# schematic.net
KiCad netlist of a schematic drawn in Altium Designer
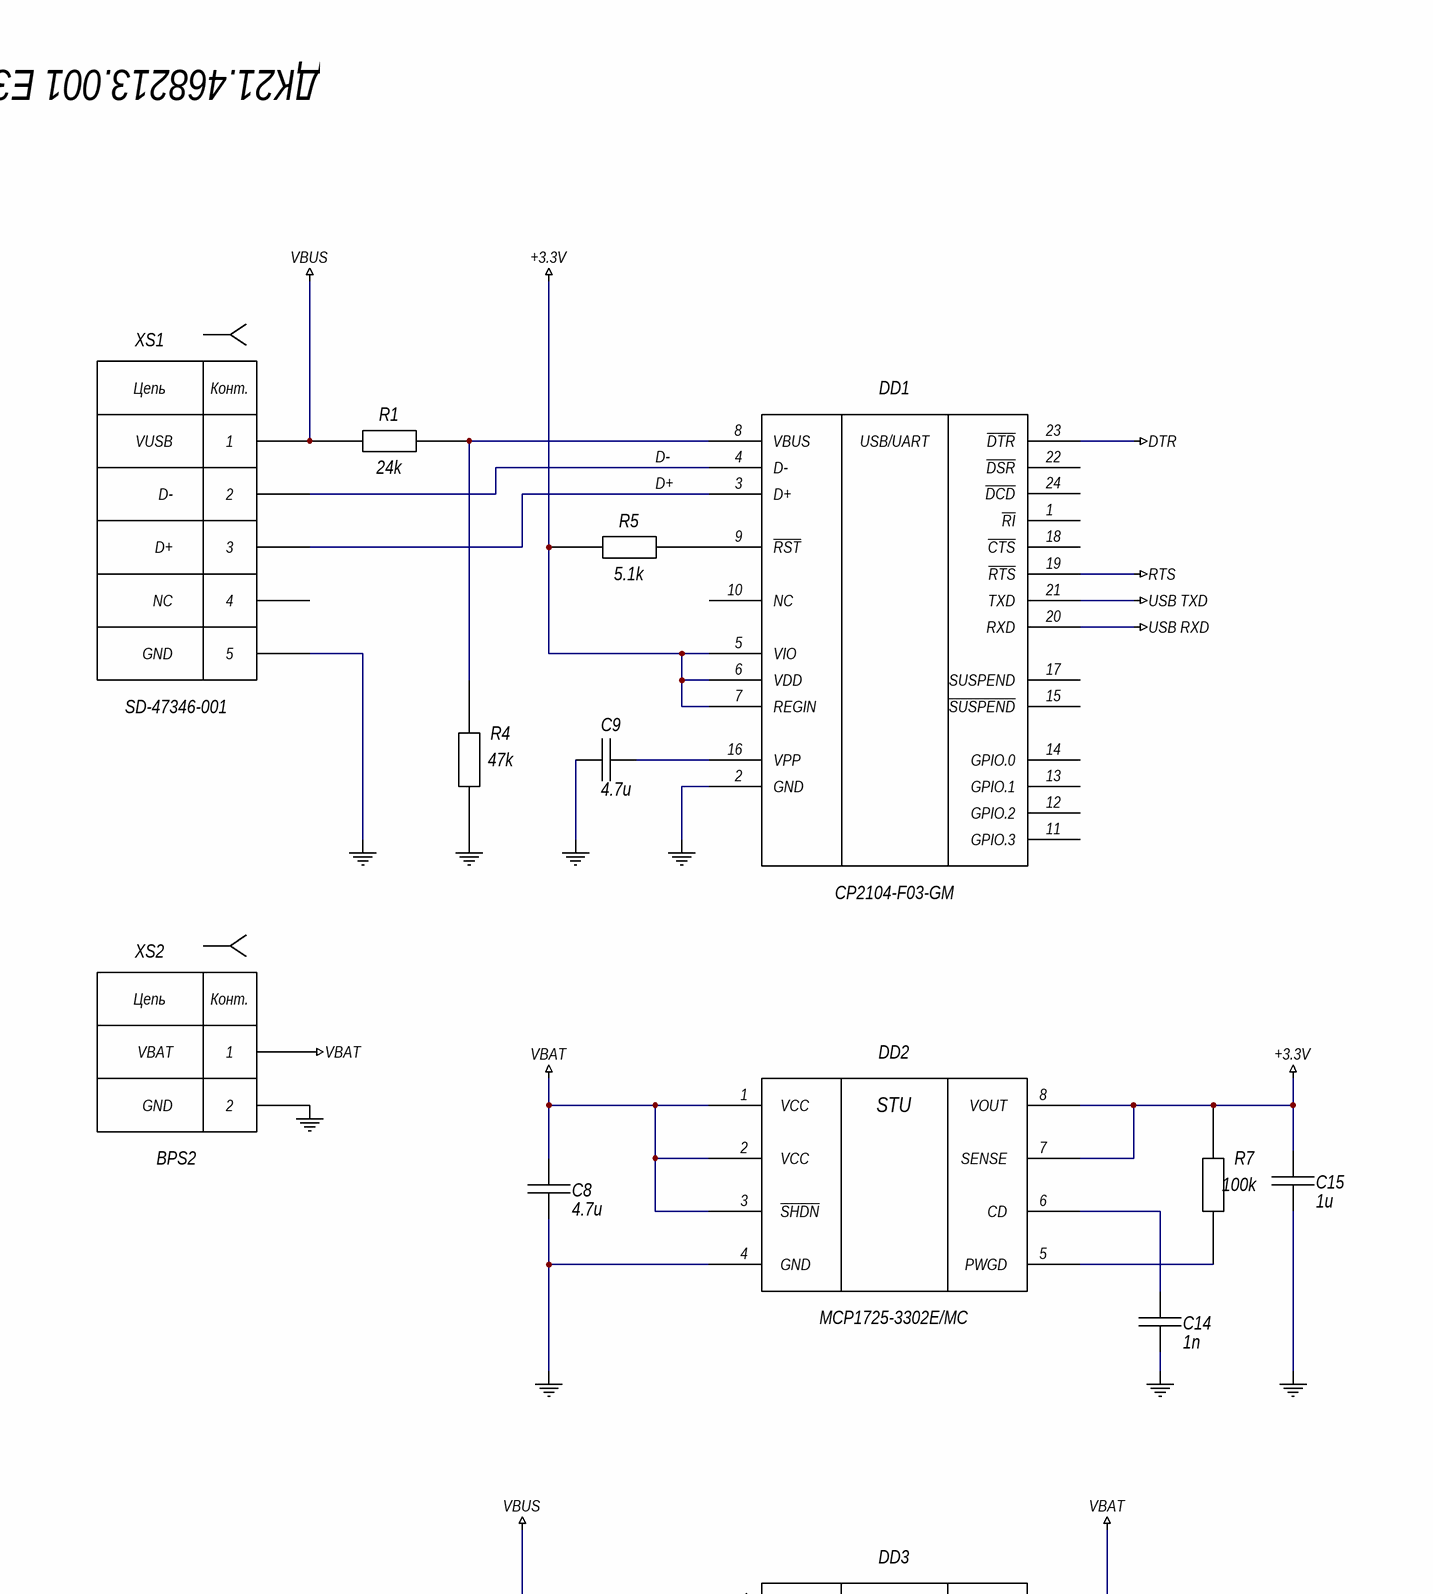
[diagram p0: schematic.SchDoc, top left]
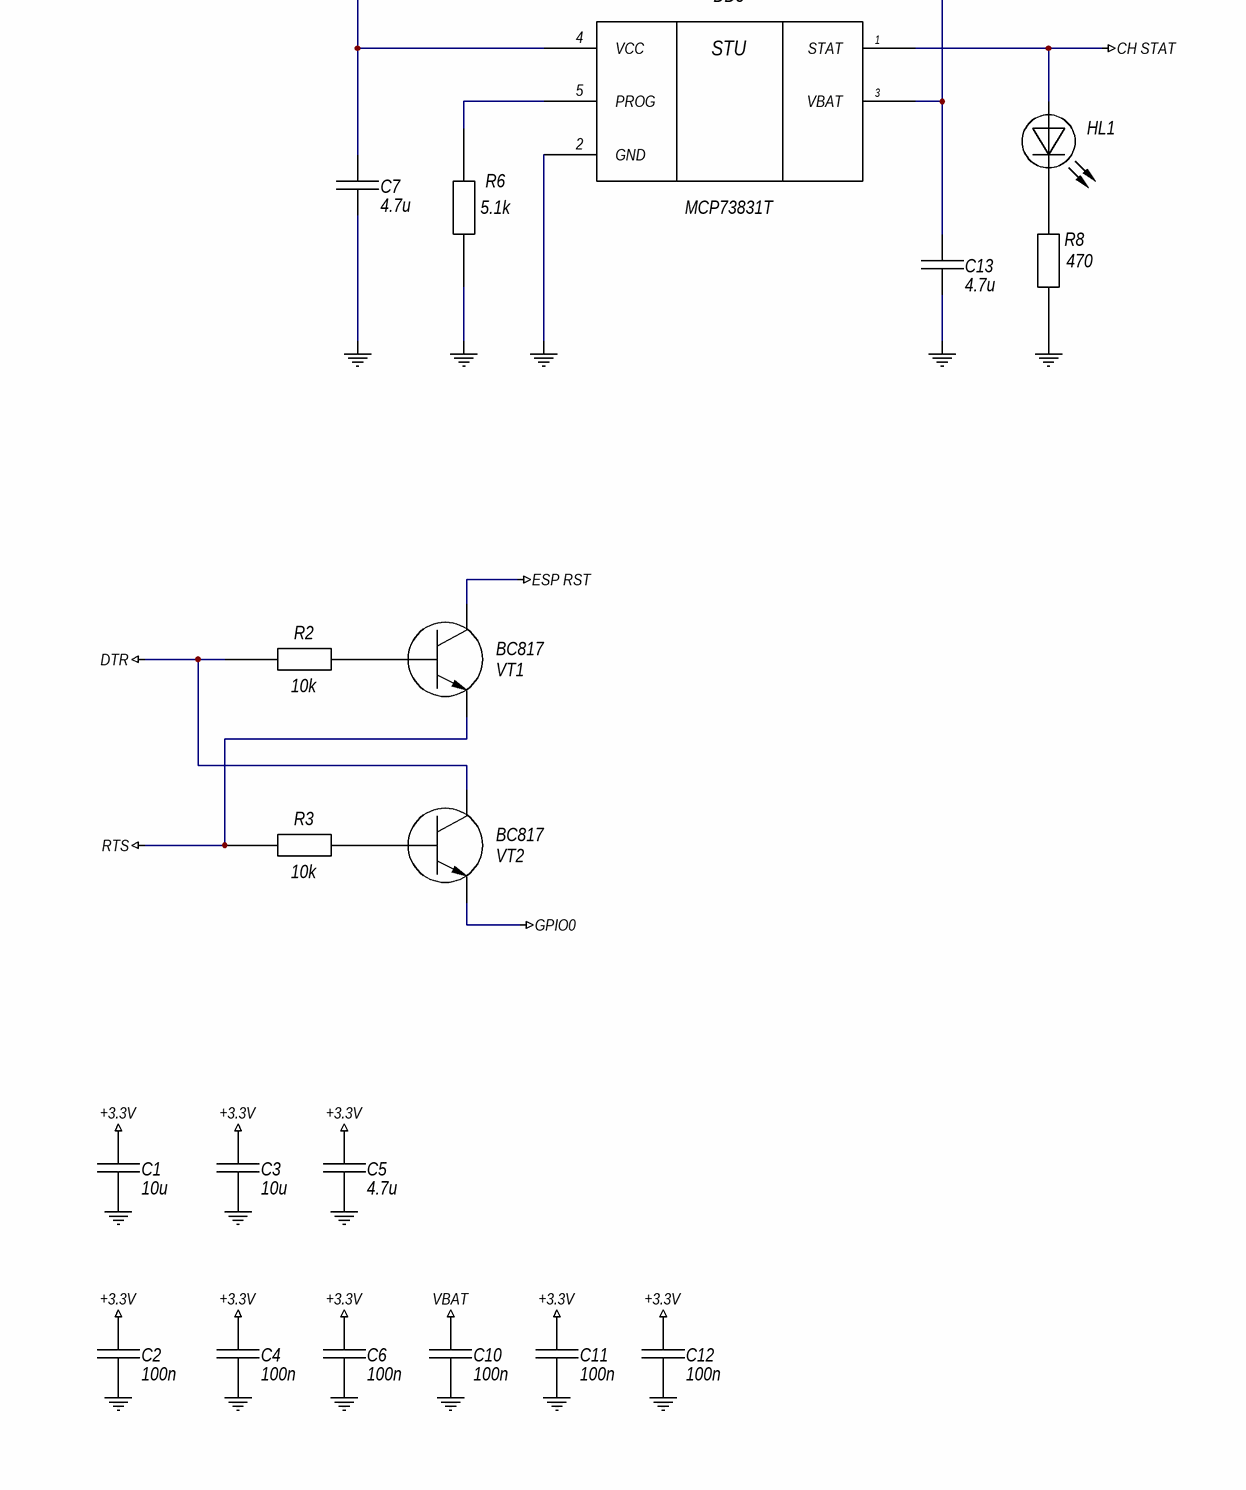
[diagram p1: schematic.SchDoc, bottom left]
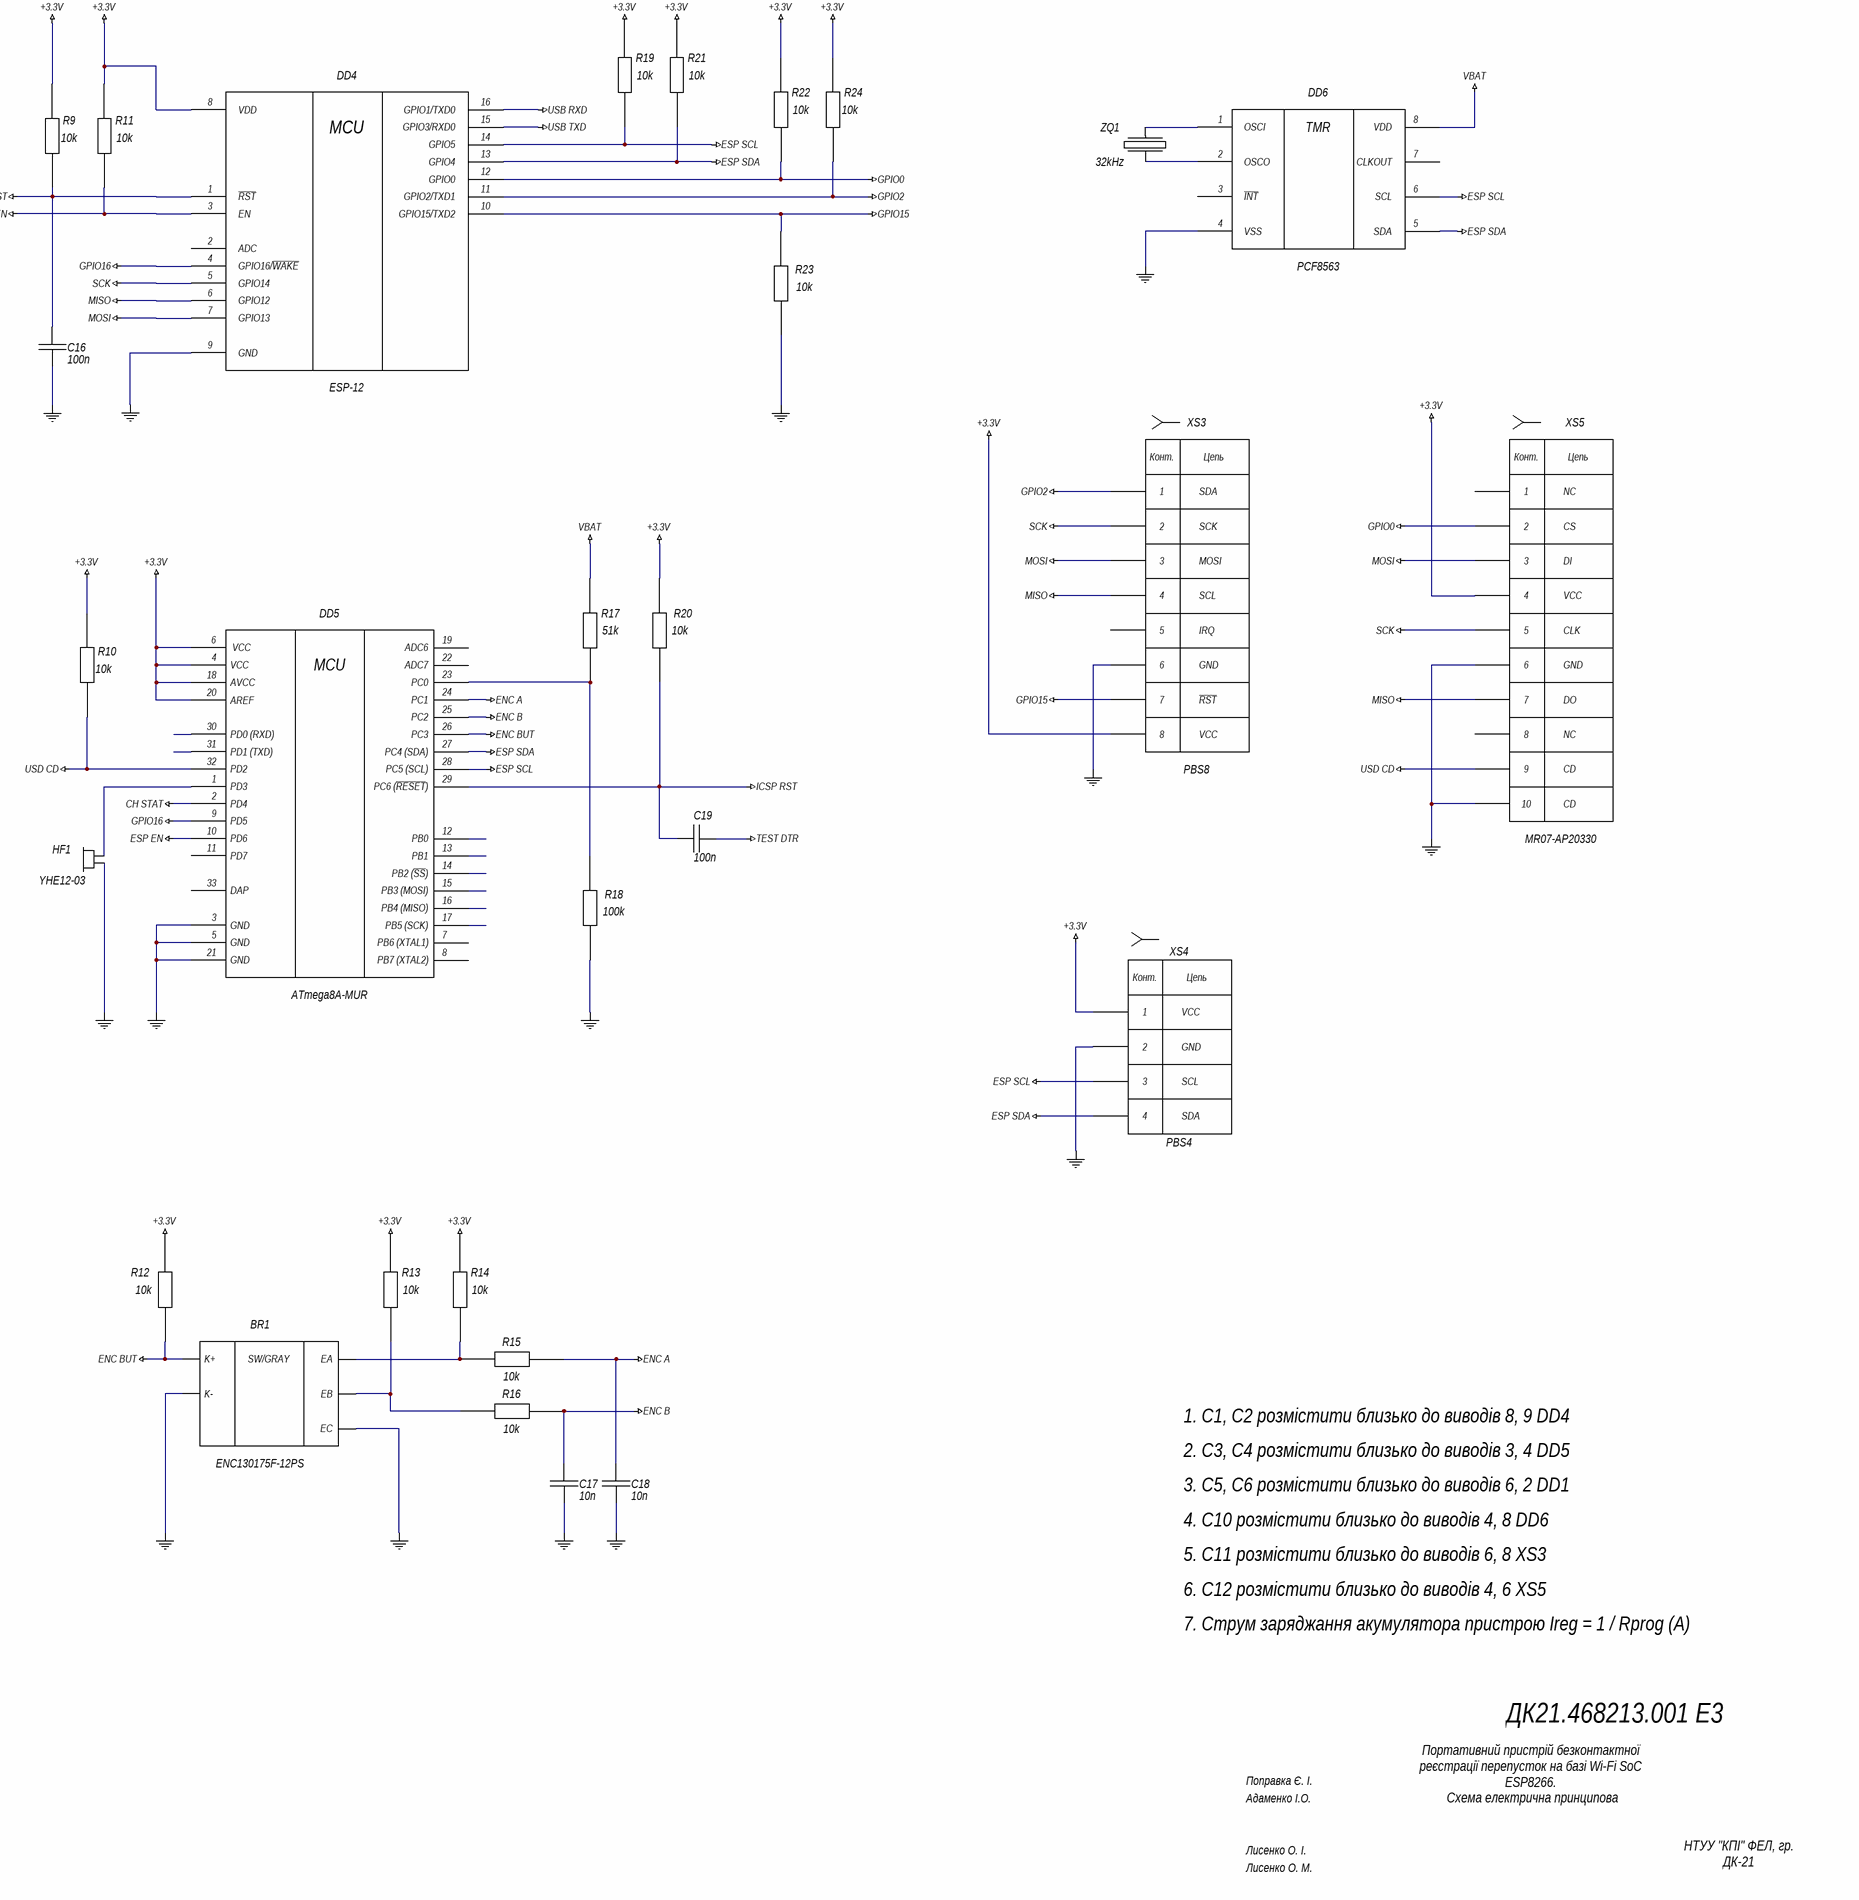
[diagram p2: schematic.SchDoc, bottom right]

(export (version "E")
  (design (tool "Eeschema 10.0.6"))
  (components
    (comp (ref "BR1")
      (value "ENC130175F-12PS")
      (footprint "ENCODER_LED_2")
      (libsource (lib "Symbols GOST") (part "ENC130175F-12PS"))
    )
    (comp (ref "C1")
      (value "10u")
      (footprint "RES0603")
      (description "Chip capasitor")
      (fields (field (name "PART NUMBER") "GRJ32ER71H475KE11") (field (name "VOLTAGE") "50V"))
      (libsource (lib "Symbols GOST") (part "C0805"))
    )
    (comp (ref "C2")
      (value "100n")
      (footprint "RES0603")
      (description "Chip capasitor")
      (fields (field (name "PART NUMBER") "GRJ32ER71H475KE11") (field (name "VOLTAGE") "50V"))
      (libsource (lib "Symbols GOST") (part "C0805"))
    )
    (comp (ref "C3")
      (value "10u")
      (footprint "RES0603")
      (description "Chip capasitor")
      (fields (field (name "PART NUMBER") "GRJ32ER71H475KE11") (field (name "VOLTAGE") "50V"))
      (libsource (lib "Symbols GOST") (part "C0805"))
    )
    (comp (ref "C4")
      (value "100n")
      (footprint "RES0603")
      (description "Chip capasitor")
      (fields (field (name "PART NUMBER") "GRJ32ER71H475KE11") (field (name "VOLTAGE") "50V"))
      (libsource (lib "Symbols GOST") (part "C0805"))
    )
    (comp (ref "C5")
      (value "4.7u")
      (footprint "RES0603")
      (description "Chip capasitor")
      (fields (field (name "PART NUMBER") "GRJ32ER71H475KE11") (field (name "VOLTAGE") "50V"))
      (libsource (lib "Symbols GOST") (part "C0805"))
    )
    (comp (ref "C6")
      (value "100n")
      (footprint "RES0603")
      (description "Chip capasitor")
      (fields (field (name "PART NUMBER") "GRJ32ER71H475KE11") (field (name "VOLTAGE") "50V"))
      (libsource (lib "Symbols GOST") (part "C0805"))
    )
    (comp (ref "C7")
      (value "4.7u")
      (footprint "RES0603")
      (description "Chip capasitor")
      (fields (field (name "PART NUMBER") "GRJ32ER71H475KE11") (field (name "VOLTAGE") "50V"))
      (libsource (lib "Symbols GOST") (part "C0805"))
    )
    (comp (ref "C8")
      (value "4.7u")
      (footprint "RES0603")
      (description "Chip capasitor")
      (fields (field (name "PART NUMBER") "GRJ32ER71H475KE11") (field (name "VOLTAGE") "50V"))
      (libsource (lib "Symbols GOST") (part "C0805"))
    )
    (comp (ref "C9")
      (value "4.7u")
      (footprint "RES0603")
      (description "Chip capasitor")
      (fields (field (name "PART NUMBER") "GRJ32ER71H475KE11") (field (name "VOLTAGE") "50V"))
      (libsource (lib "Symbols GOST") (part "C0805"))
    )
    (comp (ref "C10")
      (value "100n")
      (footprint "RES0603")
      (description "Chip capasitor")
      (fields (field (name "PART NUMBER") "GRJ32ER71H475KE11") (field (name "VOLTAGE") "50V"))
      (libsource (lib "Symbols GOST") (part "C0805"))
    )
    (comp (ref "C11")
      (value "100n")
      (footprint "RES0603")
      (description "Chip capasitor")
      (fields (field (name "PART NUMBER") "GRJ32ER71H475KE11") (field (name "VOLTAGE") "50V"))
      (libsource (lib "Symbols GOST") (part "C0805"))
    )
    (comp (ref "C12")
      (value "100n")
      (footprint "RES0603")
      (description "Chip capasitor")
      (fields (field (name "PART NUMBER") "GRJ32ER71H475KE11") (field (name "VOLTAGE") "50V"))
      (libsource (lib "Symbols GOST") (part "C0805"))
    )
    (comp (ref "C13")
      (value "4.7u")
      (footprint "RES0603")
      (description "Chip capasitor")
      (fields (field (name "PART NUMBER") "GRJ32ER71H475KE11") (field (name "VOLTAGE") "50V"))
      (libsource (lib "Symbols GOST") (part "C0805"))
    )
    (comp (ref "C14")
      (value "1n")
      (footprint "RES0603")
      (description "Chip capasitor")
      (fields (field (name "PART NUMBER") "GRJ32ER71H475KE11") (field (name "VOLTAGE") "50V"))
      (libsource (lib "Symbols GOST") (part "C0805"))
    )
    (comp (ref "C15")
      (value "1u")
      (footprint "RES0603")
      (description "Chip capasitor")
      (fields (field (name "PART NUMBER") "GRJ32ER71H475KE11") (field (name "VOLTAGE") "50V"))
      (libsource (lib "Symbols GOST") (part "C0805"))
    )
    (comp (ref "C16")
      (value "100n")
      (footprint "RES0603")
      (description "Chip capasitor")
      (fields (field (name "PART NUMBER") "GRJ32ER71H475KE11") (field (name "VOLTAGE") "50V"))
      (libsource (lib "Symbols GOST") (part "C0805"))
    )
    (comp (ref "C17")
      (value "10n")
      (footprint "RES0603")
      (description "Chip capasitor")
      (fields (field (name "PART NUMBER") "GRJ32ER71H475KE11") (field (name "VOLTAGE") "50V"))
      (libsource (lib "Symbols GOST") (part "C0805"))
    )
    (comp (ref "C18")
      (value "10n")
      (footprint "RES0603")
      (description "Chip capasitor")
      (fields (field (name "PART NUMBER") "GRJ32ER71H475KE11") (field (name "VOLTAGE") "50V"))
      (libsource (lib "Symbols GOST") (part "C0805"))
    )
    (comp (ref "C19")
      (value "100n")
      (footprint "RES0603")
      (description "Chip capasitor")
      (fields (field (name "PART NUMBER") "GRJ32ER71H475KE11") (field (name "VOLTAGE") "50V"))
      (libsource (lib "Symbols GOST") (part "C0805"))
    )
    (comp (ref "DD1")
      (value "CP2104-F03-GM")
      (footprint "SLAB-QFN-24-2675x2675TP_M")
      (fields (field (name "MANUFACTURER") "Silicon Labs"))
      (libsource (lib "Symbols GOST") (part "CP2104-F03-GM"))
    )
    (comp (ref "DD2")
      (value "MCP1725-3302E/MC")
      (footprint "SOIC127P600X175-8N")
      (description "MCP1725-3302E/MC ULDO")
      (libsource (lib "Symbols GOST") (part "MCP1725-3302E/MC"))
    )
    (comp (ref "DD3")
      (value "MCP73831T")
      (footprint "SOT95P270X145-5N")
      (description "MCP73831T Li-ion/Li-po charger")
      (fields (field (name "PART NUMBER") "MCP73831/2  SOT-23-5"))
      (libsource (lib "Symbols GOST") (part "MCP73831T"))
    )
    (comp (ref "DD4")
      (value "ESP-12")
      (footprint "ESP_12_E")
      (description "ESP-12 Wi-Fi Module")
      (libsource (lib "Symbols GOST") (part "ESP-12E"))
    )
    (comp (ref "DD5")
      (value "ATmega8A-MUR")
      (footprint "QFN127P600-8N")
      (libsource (lib "Symbols GOST") (part "ATmega8A-MUR"))
    )
    (comp (ref "DD6")
      (value "PCF8563")
      (footprint "SOIC8")
      (fields (field (name "PART NUMBER") "MCP1725-3302E/MC"))
      (libsource (lib "Symbols GOST") (part "PCF8563"))
    )
    (comp (ref "HF1")
      (value "YHE12-03")
      (footprint "PCBComponent_1")
      (description "Пьезоизлучатель")
      (libsource (lib "Symbols GOST") (part "HF"))
    )
    (comp (ref "HL1")
      (value "~")
      (footprint "RES0603")
      (description "Светодиод")
      (fields (field (name "PART NUMBER") "KP-2012VGC-A"))
      (libsource (lib "Symbols GOST") (part "HL_02"))
    )
    (comp (ref "R1")
      (value "24k")
      (footprint "RES0603")
      (description "Резистор")
      (fields (field (name "PART NUMBER") "RC0805JR-070RL") (field (name "VOLTAGE") "150V"))
      (libsource (lib "") (part "R0805_3"))
    )
    (comp (ref "R2")
      (value "10k")
      (footprint "RES0603")
      (description "Резистор")
      (fields (field (name "PART NUMBER") "RC0805JR-070RL") (field (name "VOLTAGE") "150V"))
      (libsource (lib "") (part "R0805_2"))
    )
    (comp (ref "R3")
      (value "10k")
      (footprint "RES0603")
      (description "Резистор")
      (fields (field (name "PART NUMBER") "RC0805JR-070RL") (field (name "VOLTAGE") "150V"))
      (libsource (lib "") (part "R0805_2"))
    )
    (comp (ref "R4")
      (value "47k")
      (footprint "RES0603")
      (description "Резистор")
      (fields (field (name "PART NUMBER") "RC0805JR-070RL") (field (name "VOLTAGE") "150V"))
      (libsource (lib "Symbols GOST") (part "R0805"))
    )
    (comp (ref "R5")
      (value "5.1k")
      (footprint "RES0603")
      (description "Резистор")
      (fields (field (name "PART NUMBER") "RC0805JR-070RL") (field (name "VOLTAGE") "150V"))
      (libsource (lib "") (part "R0805_1"))
    )
    (comp (ref "R6")
      (value "5.1k")
      (footprint "RES0603")
      (description "Резистор")
      (fields (field (name "PART NUMBER") "RC0805JR-070RL") (field (name "VOLTAGE") "150V"))
      (libsource (lib "Symbols GOST") (part "R0805"))
    )
    (comp (ref "R7")
      (value "100k")
      (footprint "RES0603")
      (description "Резистор")
      (fields (field (name "PART NUMBER") "RC0805JR-070RL") (field (name "VOLTAGE") "150V"))
      (libsource (lib "Symbols GOST") (part "R0805"))
    )
    (comp (ref "R8")
      (value "470")
      (footprint "RES0603")
      (description "Резистор")
      (fields (field (name "PART NUMBER") "RC0805JR-070RL") (field (name "VOLTAGE") "150V"))
      (libsource (lib "Symbols GOST") (part "R0805"))
    )
    (comp (ref "R9")
      (value "10k")
      (footprint "RES0603")
      (description "Резистор")
      (fields (field (name "PART NUMBER") "RC0805JR-070RL") (field (name "VOLTAGE") "150V"))
      (libsource (lib "Symbols GOST") (part "R0805"))
    )
    (comp (ref "R10")
      (value "10k")
      (footprint "RES0603")
      (description "Резистор")
      (fields (field (name "PART NUMBER") "RC0805JR-070RL") (field (name "VOLTAGE") "150V"))
      (libsource (lib "Symbols GOST") (part "R0805"))
    )
    (comp (ref "R11")
      (value "10k")
      (footprint "RES0603")
      (description "Резистор")
      (fields (field (name "PART NUMBER") "RC0805JR-070RL") (field (name "VOLTAGE") "150V"))
      (libsource (lib "Symbols GOST") (part "R0805"))
    )
    (comp (ref "R12")
      (value "10k")
      (footprint "RES0603")
      (description "Резистор")
      (fields (field (name "PART NUMBER") "RC0805JR-070RL") (field (name "VOLTAGE") "150V"))
      (libsource (lib "") (part "R0805_1"))
    )
    (comp (ref "R13")
      (value "10k")
      (footprint "RES0603")
      (description "Резистор")
      (fields (field (name "PART NUMBER") "RC0805JR-070RL") (field (name "VOLTAGE") "150V"))
      (libsource (lib "Symbols GOST") (part "R0805"))
    )
    (comp (ref "R14")
      (value "10k")
      (footprint "RES0603")
      (description "Резистор")
      (fields (field (name "PART NUMBER") "RC0805JR-070RL") (field (name "VOLTAGE") "150V"))
      (libsource (lib "Symbols GOST") (part "R0805"))
    )
    (comp (ref "R15")
      (value "10k")
      (footprint "RES0603")
      (description "Резистор")
      (fields (field (name "PART NUMBER") "RC0805JR-070RL") (field (name "VOLTAGE") "150V"))
      (libsource (lib "") (part "R0805_1"))
    )
    (comp (ref "R16")
      (value "10k")
      (footprint "RES0603")
      (description "Резистор")
      (fields (field (name "PART NUMBER") "RC0805JR-070RL") (field (name "VOLTAGE") "150V"))
      (libsource (lib "") (part "R0805_1"))
    )
    (comp (ref "R17")
      (value "51k")
      (footprint "RES0603")
      (description "Резистор")
      (fields (field (name "PART NUMBER") "RC0805JR-070RL") (field (name "VOLTAGE") "150V"))
      (libsource (lib "Symbols GOST") (part "R0805"))
    )
    (comp (ref "R18")
      (value "100k")
      (footprint "RES0603")
      (description "Резистор")
      (fields (field (name "PART NUMBER") "RC0805JR-070RL") (field (name "VOLTAGE") "150V"))
      (libsource (lib "Symbols GOST") (part "R0805"))
    )
    (comp (ref "R19")
      (value "10k")
      (footprint "RES0603")
      (description "Резистор")
      (fields (field (name "PART NUMBER") "RC0805JR-070RL") (field (name "VOLTAGE") "150V"))
      (libsource (lib "Symbols GOST") (part "R0805"))
    )
    (comp (ref "R20")
      (value "10k")
      (footprint "RES0603")
      (description "Резистор")
      (fields (field (name "PART NUMBER") "RC0805JR-070RL") (field (name "VOLTAGE") "150V"))
      (libsource (lib "Symbols GOST") (part "R0805"))
    )
    (comp (ref "R21")
      (value "10k")
      (footprint "RES0603")
      (description "Резистор")
      (fields (field (name "PART NUMBER") "RC0805JR-070RL") (field (name "VOLTAGE") "150V"))
      (libsource (lib "Symbols GOST") (part "R0805"))
    )
    (comp (ref "R22")
      (value "10k")
      (footprint "RES0603")
      (description "Резистор")
      (fields (field (name "PART NUMBER") "RC0805JR-070RL") (field (name "VOLTAGE") "150V"))
      (libsource (lib "Symbols GOST") (part "R0805"))
    )
    (comp (ref "R23")
      (value "10k")
      (footprint "RES0603")
      (description "Резистор")
      (fields (field (name "PART NUMBER") "RC0805JR-070RL") (field (name "VOLTAGE") "150V"))
      (libsource (lib "Symbols GOST") (part "R0805"))
    )
    (comp (ref "R24")
      (value "10k")
      (footprint "RES0603")
      (description "Резистор")
      (fields (field (name "PART NUMBER") "RC0805JR-070RL") (field (name "VOLTAGE") "150V"))
      (libsource (lib "Symbols GOST") (part "R0805"))
    )
    (comp (ref "VT1")
      (value "BC817")
      (footprint "SOT95P245X110-3N")
      (description "Транзистор биполярный, NPN")
      (libsource (lib "Symbols GOST") (part "VT_01"))
    )
    (comp (ref "VT2")
      (value "BC817")
      (footprint "SOT95P245X110-3N")
      (description "Транзистор биполярный, NPN")
      (libsource (lib "Symbols GOST") (part "VT_01"))
    )
    (comp (ref "XS1")
      (value "SD-47346-001")
      (footprint "USB-MICROB")
      (description "micro USB")
      (fields (field (name "PART NUMBER") "RFID-RC522 MFRC522 модуль"))
      (libsource (lib "Symbols GOST") (part "usb"))
    )
    (comp (ref "XS2")
      (value "BPS2")
      (footprint "PCBComponent_1 - duplicate")
      (description "battery")
      (fields (field (name "PART NUMBER") "RFID-RC522 MFRC522 модуль"))
      (libsource (lib "Symbols GOST") (part "lipo"))
    )
    (comp (ref "XS3")
      (value "PBS8")
      (footprint "RFID-RC522")
      (description "RC522 RFID module")
      (fields (field (name "PART NUMBER") "RFID-RC522 MFRC522 модуль"))
      (libsource (lib "Symbols GOST") (part "RC522"))
    )
    (comp (ref "XS4")
      (value "PBS4")
      (footprint "SSD")
      (description "SSD1306 OLED Screen Module")
      (fields (field (name "PART NUMBER") "RFID-RC522 MFRC522 модуль"))
      (libsource (lib "Symbols GOST") (part "SSD1306"))
    )
    (comp (ref "XS5")
      (value "MR07-AP20330")
      (footprint "MICROSD Slot")
      (description "RC522 RFID module")
      (fields (field (name "PART NUMBER") "RFID-RC522 MFRC522 модуль"))
      (libsource (lib "Symbols GOST") (part "uSD"))
    )
    (comp (ref "ZQ1")
      (value "32kHz")
      (footprint "PCBComponent_1 - duplicate1")
      (description "Элемент пьезоэлектрический с двумя выводами")
      (fields (field (name "PART NUMBER") "HC49/US 16MHz"))
      (libsource (lib "Symbols GOST") (part "ZQ_01"))
    )
  )
  (nets
    (net (code "1") (name "+3.3V") (class "Default")
      (node (ref "C1") (pin "1") (pinfunction "1_1") (pintype "passive"))
      (node (ref "C11") (pin "1") (pinfunction "1_1") (pintype "passive"))
      (node (ref "C12") (pin "1") (pinfunction "1_1") (pintype "passive"))
      (node (ref "C15") (pin "1") (pinfunction "1_1") (pintype "passive"))
      (node (ref "C2") (pin "1") (pinfunction "1_1") (pintype "passive"))
      (node (ref "C3") (pin "1") (pinfunction "1_1") (pintype "passive"))
      (node (ref "C4") (pin "1") (pinfunction "1_1") (pintype "passive"))
      (node (ref "C5") (pin "1") (pinfunction "1_1") (pintype "passive"))
      (node (ref "C6") (pin "1") (pinfunction "1_1") (pintype "passive"))
      (node (ref "DD1") (pin "5") (pinfunction "VIO_5") (pintype "passive"))
      (node (ref "DD1") (pin "6") (pinfunction "VDD_6") (pintype "passive"))
      (node (ref "DD1") (pin "7") (pinfunction "REGIN_7") (pintype "passive"))
      (node (ref "DD2") (pin "7") (pinfunction "SENSE_7") (pintype "passive"))
      (node (ref "DD2") (pin "8") (pinfunction "VOUT_8") (pintype "passive"))
      (node (ref "DD4") (pin "8") (pinfunction "VDD_8") (pintype "passive"))
      (node (ref "DD5") (pin "18") (pinfunction "AVCC_18") (pintype "passive"))
      (node (ref "DD5") (pin "20") (pinfunction "AREF_20") (pintype "passive"))
      (node (ref "DD5") (pin "4") (pinfunction "VCC_4") (pintype "passive"))
      (node (ref "DD5") (pin "6") (pinfunction "VCC_6") (pintype "passive"))
      (node (ref "R10") (pin "2") (pinfunction "Terminal_B_2") (pintype "passive"))
      (node (ref "R11") (pin "2") (pinfunction "Terminal_B_2") (pintype "passive"))
      (node (ref "R12") (pin "2") (pinfunction "Terminal_B_2") (pintype "passive"))
      (node (ref "R13") (pin "2") (pinfunction "Terminal_B_2") (pintype "passive"))
      (node (ref "R14") (pin "2") (pinfunction "Terminal_B_2") (pintype "passive"))
      (node (ref "R19") (pin "2") (pinfunction "Terminal_B_2") (pintype "passive"))
      (node (ref "R20") (pin "2") (pinfunction "Terminal_B_2") (pintype "passive"))
      (node (ref "R21") (pin "2") (pinfunction "Terminal_B_2") (pintype "passive"))
      (node (ref "R22") (pin "2") (pinfunction "Terminal_B_2") (pintype "passive"))
      (node (ref "R24") (pin "2") (pinfunction "Terminal_B_2") (pintype "passive"))
      (node (ref "R5") (pin "1") (pinfunction "Terminal_A_1") (pintype "passive"))
      (node (ref "R7") (pin "2") (pinfunction "Terminal_B_2") (pintype "passive"))
      (node (ref "R9") (pin "2") (pinfunction "Terminal_B_2") (pintype "passive"))
      (node (ref "XS3") (pin "8") (pinfunction "VCC_8") (pintype "passive"))
      (node (ref "XS4") (pin "1") (pinfunction "VCC_1") (pintype "passive"))
      (node (ref "XS5") (pin "4") (pinfunction "VCC_4") (pintype "passive"))
    )
    (net (code "2") (name "/D+") (class "Default")
      (node (ref "DD1") (pin "3") (pinfunction "D+_3") (pintype "passive"))
      (node (ref "XS1") (pin "3") (pinfunction "D+_3") (pintype "passive"))
    )
    (net (code "3") (name "/D-") (class "Default")
      (node (ref "DD1") (pin "4") (pinfunction "D-_4") (pintype "passive"))
      (node (ref "XS1") (pin "2") (pinfunction "D-_2") (pintype "passive"))
    )
    (net (code "4") (name "CH STAT") (class "Default")
      (node (ref "DD3") (pin "1") (pinfunction "STAT_1") (pintype "passive"))
      (node (ref "DD5") (pin "2") (pinfunction "PD4_2") (pintype "passive"))
      (node (ref "HL1") (pin "1") (pinfunction "A_1") (pintype "passive"))
    )
    (net (code "5") (name "DTR") (class "Default")
      (node (ref "DD1") (pin "23") (pinfunction "~{DTR}_23") (pintype "passive"))
      (node (ref "R2") (pin "2") (pinfunction "Terminal_B_2") (pintype "passive"))
      (node (ref "VT2") (pin "3") (pinfunction "K_3") (pintype "passive"))
    )
    (net (code "6") (name "ENC A") (class "Default")
      (node (ref "C18") (pin "1") (pinfunction "1_1") (pintype "passive"))
      (node (ref "DD5") (pin "24") (pinfunction "PC1_24") (pintype "passive"))
      (node (ref "R15") (pin "2") (pinfunction "Terminal_B_2") (pintype "passive"))
    )
    (net (code "7") (name "ENC B") (class "Default")
      (node (ref "C17") (pin "1") (pinfunction "1_1") (pintype "passive"))
      (node (ref "DD5") (pin "25") (pinfunction "PC2_25") (pintype "passive"))
      (node (ref "R16") (pin "2") (pinfunction "Terminal_B_2") (pintype "passive"))
    )
    (net (code "8") (name "ENC BUT") (class "Default")
      (node (ref "BR1") (pin "K+") (pinfunction "K+_K+") (pintype "passive"))
      (node (ref "DD5") (pin "26") (pinfunction "PC3_26") (pintype "passive"))
      (node (ref "R12") (pin "1") (pinfunction "Terminal_A_1") (pintype "passive"))
    )
    (net (code "9") (name "ESP EN") (class "Default")
      (node (ref "DD4") (pin "3") (pinfunction "EN_3") (pintype "passive"))
      (node (ref "DD5") (pin "10") (pinfunction "PD6_10") (pintype "passive"))
      (node (ref "R11") (pin "1") (pinfunction "Terminal_A_1") (pintype "passive"))
    )
    (net (code "10") (name "ESP RST") (class "Default")
      (node (ref "C16") (pin "1") (pinfunction "1_1") (pintype "passive"))
      (node (ref "DD4") (pin "1") (pinfunction "~{RST}_1") (pintype "passive"))
      (node (ref "R9") (pin "1") (pinfunction "Terminal_A_1") (pintype "passive"))
      (node (ref "VT1") (pin "3") (pinfunction "K_3") (pintype "passive"))
    )
    (net (code "11") (name "ESP SCL") (class "Default")
      (node (ref "DD4") (pin "14") (pinfunction "GPIO5_14") (pintype "passive"))
      (node (ref "DD5") (pin "28") (pinfunction "PC5_(SCL)_28") (pintype "passive"))
      (node (ref "DD6") (pin "6") (pinfunction "SCL_6") (pintype "passive"))
      (node (ref "R19") (pin "1") (pinfunction "Terminal_A_1") (pintype "passive"))
      (node (ref "XS4") (pin "3") (pinfunction "SCL_3") (pintype "passive"))
    )
    (net (code "12") (name "ESP SDA") (class "Default")
      (node (ref "DD4") (pin "13") (pinfunction "GPIO4_13") (pintype "passive"))
      (node (ref "DD5") (pin "27") (pinfunction "PC4_(SDA)_27") (pintype "passive"))
      (node (ref "DD6") (pin "5") (pinfunction "SDA_5") (pintype "passive"))
      (node (ref "R21") (pin "1") (pinfunction "Terminal_A_1") (pintype "passive"))
      (node (ref "XS4") (pin "4") (pinfunction "SDA_4") (pintype "passive"))
    )
    (net (code "13") (name "GND") (class "Default")
      (node (ref "BR1") (pin "EC") (pinfunction "EC_EC") (pintype "passive"))
      (node (ref "BR1") (pin "K-") (pinfunction "K-_K-") (pintype "passive"))
      (node (ref "C1") (pin "2") (pinfunction "2_2") (pintype "passive"))
      (node (ref "C10") (pin "2") (pinfunction "2_2") (pintype "passive"))
      (node (ref "C11") (pin "2") (pinfunction "2_2") (pintype "passive"))
      (node (ref "C12") (pin "2") (pinfunction "2_2") (pintype "passive"))
      (node (ref "C13") (pin "2") (pinfunction "2_2") (pintype "passive"))
      (node (ref "C14") (pin "2") (pinfunction "2_2") (pintype "passive"))
      (node (ref "C15") (pin "2") (pinfunction "2_2") (pintype "passive"))
      (node (ref "C16") (pin "2") (pinfunction "2_2") (pintype "passive"))
      (node (ref "C17") (pin "2") (pinfunction "2_2") (pintype "passive"))
      (node (ref "C18") (pin "2") (pinfunction "2_2") (pintype "passive"))
      (node (ref "C2") (pin "2") (pinfunction "2_2") (pintype "passive"))
      (node (ref "C3") (pin "2") (pinfunction "2_2") (pintype "passive"))
      (node (ref "C4") (pin "2") (pinfunction "2_2") (pintype "passive"))
      (node (ref "C5") (pin "2") (pinfunction "2_2") (pintype "passive"))
      (node (ref "C6") (pin "2") (pinfunction "2_2") (pintype "passive"))
      (node (ref "C7") (pin "2") (pinfunction "2_2") (pintype "passive"))
      (node (ref "C8") (pin "2") (pinfunction "2_2") (pintype "passive"))
      (node (ref "C9") (pin "2") (pinfunction "2_2") (pintype "passive"))
      (node (ref "DD1") (pin "2") (pinfunction "GND_2") (pintype "passive"))
      (node (ref "DD2") (pin "4") (pinfunction "GND_4") (pintype "passive"))
      (node (ref "DD3") (pin "2") (pinfunction "GND_2") (pintype "passive"))
      (node (ref "DD4") (pin "9") (pinfunction "GND_9") (pintype "passive"))
      (node (ref "DD5") (pin "21") (pinfunction "GND_21") (pintype "passive"))
      (node (ref "DD5") (pin "3") (pinfunction "GND_3") (pintype "passive"))
      (node (ref "DD5") (pin "5") (pinfunction "GND_5") (pintype "passive"))
      (node (ref "DD6") (pin "4") (pinfunction "VSS_4") (pintype "passive"))
      (node (ref "HF1") (pin "1") (pinfunction "Terminal_A_1") (pintype "passive"))
      (node (ref "R18") (pin "1") (pinfunction "Terminal_A_1") (pintype "passive"))
      (node (ref "R23") (pin "1") (pinfunction "Terminal_A_1") (pintype "passive"))
      (node (ref "R4") (pin "1") (pinfunction "Terminal_A_1") (pintype "passive"))
      (node (ref "R6") (pin "1") (pinfunction "Terminal_A_1") (pintype "passive"))
      (node (ref "R8") (pin "1") (pinfunction "Terminal_A_1") (pintype "passive"))
      (node (ref "XS1") (pin "5") (pinfunction "GND_5") (pintype "passive"))
      (node (ref "XS2") (pin "2") (pinfunction "GND_2") (pintype "passive"))
      (node (ref "XS3") (pin "6") (pinfunction "GND_6") (pintype "passive"))
      (node (ref "XS4") (pin "2") (pinfunction "GND_2") (pintype "passive"))
      (node (ref "XS5") (pin "10") (pinfunction "CD_10") (pintype "passive"))
      (node (ref "XS5") (pin "6") (pinfunction "GND_6") (pintype "passive"))
    )
    (net (code "14") (name "GPIO0") (class "Default")
      (node (ref "DD4") (pin "12") (pinfunction "GPIO0_12") (pintype "passive"))
      (node (ref "R22") (pin "1") (pinfunction "Terminal_A_1") (pintype "passive"))
      (node (ref "VT2") (pin "2") (pinfunction "E_2") (pintype "passive"))
      (node (ref "XS5") (pin "2") (pinfunction "CS_2") (pintype "passive"))
    )
    (net (code "15") (name "GPIO2") (class "Default")
      (node (ref "DD4") (pin "11") (pinfunction "GPIO2/TXD1_11") (pintype "passive"))
      (node (ref "R24") (pin "1") (pinfunction "Terminal_A_1") (pintype "passive"))
      (node (ref "XS3") (pin "1") (pinfunction "SDA_1") (pintype "passive"))
    )
    (net (code "16") (name "GPIO15") (class "Default")
      (node (ref "DD4") (pin "10") (pinfunction "GPIO15/TXD2_10") (pintype "passive"))
      (node (ref "R23") (pin "2") (pinfunction "Terminal_B_2") (pintype "passive"))
      (node (ref "XS3") (pin "7") (pinfunction "~{RST}_7") (pintype "passive"))
    )
    (net (code "17") (name "GPIO16") (class "Default")
      (node (ref "DD4") (pin "4") (pinfunction "GPIO16/~{WAKE}_4") (pintype "passive"))
      (node (ref "DD5") (pin "9") (pinfunction "PD5_9") (pintype "passive"))
    )
    (net (code "18") (name "ICSP RST") (class "Default")
      (node (ref "C19") (pin "1") (pinfunction "1_1") (pintype "passive"))
      (node (ref "DD5") (pin "29") (pinfunction "PC6_(~{RESET})_29") (pintype "passive"))
      (node (ref "R20") (pin "1") (pinfunction "Terminal_A_1") (pintype "passive"))
    )
    (net (code "19") (name "MISO") (class "Default")
      (node (ref "DD4") (pin "6") (pinfunction "GPIO12_6") (pintype "passive"))
      (node (ref "XS3") (pin "4") (pinfunction "SCL_4") (pintype "passive"))
      (node (ref "XS5") (pin "7") (pinfunction "DO_7") (pintype "passive"))
    )
    (net (code "20") (name "MOSI") (class "Default")
      (node (ref "DD4") (pin "7") (pinfunction "GPIO13_7") (pintype "passive"))
      (node (ref "XS3") (pin "3") (pinfunction "MOSI_3") (pintype "passive"))
      (node (ref "XS5") (pin "3") (pinfunction "DI_3") (pintype "passive"))
    )
    (net (code "21") (name "Net-(DD1-VBUS)") (class "Default")
      (node (ref "DD1") (pin "8") (pinfunction "VBUS_8") (pintype "passive"))
      (node (ref "R1") (pin "1") (pinfunction "Terminal_A_1") (pintype "passive"))
      (node (ref "R4") (pin "2") (pinfunction "Terminal_B_2") (pintype "passive"))
    )
    (net (code "22") (name "Net-(DD1-VPP)") (class "Default")
      (node (ref "C9") (pin "1") (pinfunction "1_1") (pintype "passive"))
      (node (ref "DD1") (pin "16") (pinfunction "VPP_16") (pintype "passive"))
    )
    (net (code "23") (name "Net-(DD1-~{RST})") (class "Default")
      (node (ref "DD1") (pin "9") (pinfunction "~{RST}_9") (pintype "passive"))
      (node (ref "R5") (pin "2") (pinfunction "Terminal_B_2") (pintype "passive"))
    )
    (net (code "24") (name "Net-(DD2-CD)") (class "Default")
      (node (ref "C14") (pin "1") (pinfunction "1_1") (pintype "passive"))
      (node (ref "DD2") (pin "6") (pinfunction "CD_6") (pintype "passive"))
    )
    (net (code "25") (name "Net-(DD2-PWGD)") (class "Default")
      (node (ref "DD2") (pin "5") (pinfunction "PWGD_5") (pintype "passive"))
      (node (ref "R7") (pin "1") (pinfunction "Terminal_A_1") (pintype "passive"))
    )
    (net (code "26") (name "Net-(DD3-PROG)") (class "Default")
      (node (ref "DD3") (pin "5") (pinfunction "PROG_5") (pintype "passive"))
      (node (ref "R6") (pin "2") (pinfunction "Terminal_B_2") (pintype "passive"))
    )
    (net (code "27") (name "Net-(DD5-PC0)") (class "Default")
      (node (ref "DD5") (pin "23") (pinfunction "PC0_23") (pintype "passive"))
      (node (ref "R17") (pin "1") (pinfunction "Terminal_A_1") (pintype "passive"))
      (node (ref "R18") (pin "2") (pinfunction "Terminal_B_2") (pintype "passive"))
    )
    (net (code "28") (name "Net-(DD5-PD3)") (class "Default")
      (node (ref "DD5") (pin "1") (pinfunction "PD3_1") (pintype "passive"))
      (node (ref "HF1") (pin "2") (pinfunction "Terminal_B_2") (pintype "passive"))
    )
    (net (code "29") (name "Net-(DD6-OSCI)") (class "Default")
      (node (ref "DD6") (pin "1") (pinfunction "OSCI_1") (pintype "passive"))
      (node (ref "ZQ1") (pin "1") (pintype "passive"))
    )
    (net (code "30") (name "Net-(DD6-OSCO)") (class "Default")
      (node (ref "DD6") (pin "2") (pinfunction "OSCO_2") (pintype "passive"))
      (node (ref "ZQ1") (pin "2") (pintype "passive"))
    )
    (net (code "31") (name "Net-(HL1-K)") (class "Default")
      (node (ref "HL1") (pin "2") (pinfunction "K_2") (pintype "passive"))
      (node (ref "R8") (pin "2") (pinfunction "Terminal_B_2") (pintype "passive"))
    )
    (net (code "32") (name "Net-(R2-Terminal_A)") (class "Default")
      (node (ref "R2") (pin "1") (pinfunction "Terminal_A_1") (pintype "passive"))
      (node (ref "VT1") (pin "1") (pinfunction "B_1") (pintype "passive"))
    )
    (net (code "33") (name "Net-(R3-Terminal_A)") (class "Default")
      (node (ref "R3") (pin "1") (pinfunction "Terminal_A_1") (pintype "passive"))
      (node (ref "VT2") (pin "1") (pinfunction "B_1") (pintype "passive"))
    )
    (net (code "34") (name "Net-(R13-Terminal_A)") (class "Default")
      (node (ref "BR1") (pin "EB") (pinfunction "EB_EB") (pintype "passive"))
      (node (ref "R13") (pin "1") (pinfunction "Terminal_A_1") (pintype "passive"))
      (node (ref "R16") (pin "1") (pinfunction "Terminal_A_1") (pintype "passive"))
    )
    (net (code "35") (name "Net-(R14-Terminal_A)") (class "Default")
      (node (ref "BR1") (pin "EA") (pinfunction "EA_EA") (pintype "passive"))
      (node (ref "R14") (pin "1") (pinfunction "Terminal_A_1") (pintype "passive"))
      (node (ref "R15") (pin "1") (pinfunction "Terminal_A_1") (pintype "passive"))
    )
    (net (code "36") (name "RTS") (class "Default")
      (node (ref "DD1") (pin "19") (pinfunction "~{RTS}_19") (pintype "passive"))
      (node (ref "R3") (pin "2") (pinfunction "Terminal_B_2") (pintype "passive"))
      (node (ref "VT1") (pin "2") (pinfunction "E_2") (pintype "passive"))
    )
    (net (code "37") (name "SCK") (class "Default")
      (node (ref "DD4") (pin "5") (pinfunction "GPIO14_5") (pintype "passive"))
      (node (ref "XS3") (pin "2") (pinfunction "SCK_2") (pintype "passive"))
      (node (ref "XS5") (pin "5") (pinfunction "CLK_5") (pintype "passive"))
    )
    (net (code "38") (name "TEST DTR") (class "Default")
      (node (ref "C19") (pin "2") (pinfunction "2_2") (pintype "passive"))
    )
    (net (code "39") (name "USB RXD") (class "Default")
      (node (ref "DD1") (pin "20") (pinfunction "RXD_20") (pintype "passive"))
      (node (ref "DD4") (pin "16") (pinfunction "GPIO1/TXD0_16") (pintype "passive"))
    )
    (net (code "40") (name "USB TXD") (class "Default")
      (node (ref "DD1") (pin "21") (pinfunction "TXD_21") (pintype "passive"))
      (node (ref "DD4") (pin "15") (pinfunction "GPIO3/RXD0_15") (pintype "passive"))
    )
    (net (code "41") (name "USD CD") (class "Default")
      (node (ref "DD5") (pin "32") (pinfunction "PD2_32") (pintype "passive"))
      (node (ref "R10") (pin "1") (pinfunction "Terminal_A_1") (pintype "passive"))
      (node (ref "XS5") (pin "9") (pinfunction "CD_9") (pintype "passive"))
    )
    (net (code "42") (name "VBAT") (class "Default")
      (node (ref "C10") (pin "1") (pinfunction "1_1") (pintype "passive"))
      (node (ref "C13") (pin "1") (pinfunction "1_1") (pintype "passive"))
      (node (ref "C8") (pin "1") (pinfunction "1_1") (pintype "passive"))
      (node (ref "DD2") (pin "1") (pinfunction "VCC_1") (pintype "passive"))
      (node (ref "DD2") (pin "2") (pinfunction "VCC_2") (pintype "passive"))
      (node (ref "DD2") (pin "3") (pinfunction "~{SHDN}_3") (pintype "passive"))
      (node (ref "DD3") (pin "3") (pinfunction "VBAT_3") (pintype "passive"))
      (node (ref "DD6") (pin "8") (pinfunction "VDD_8") (pintype "passive"))
      (node (ref "R17") (pin "2") (pinfunction "Terminal_B_2") (pintype "passive"))
      (node (ref "XS2") (pin "1") (pinfunction "VBAT_1") (pintype "passive"))
    )
    (net (code "43") (name "VBUS") (class "Default")
      (node (ref "C7") (pin "1") (pinfunction "1_1") (pintype "passive"))
      (node (ref "DD3") (pin "4") (pinfunction "VCC_4") (pintype "passive"))
      (node (ref "R1") (pin "2") (pinfunction "Terminal_B_2") (pintype "passive"))
      (node (ref "XS1") (pin "1") (pinfunction "VUSB_1") (pintype "passive"))
    )
    (net (code "44") (name "unconnected-(DD1-GPIO.0-Pad14)") (class "Default")
      (node (ref "DD1") (pin "14") (pinfunction "GPIO.0_14") (pintype "passive"))
    )
    (net (code "45") (name "unconnected-(DD1-GPIO.1-Pad13)") (class "Default")
      (node (ref "DD1") (pin "13") (pinfunction "GPIO.1_13") (pintype "passive"))
    )
    (net (code "46") (name "unconnected-(DD1-GPIO.2-Pad12)") (class "Default")
      (node (ref "DD1") (pin "12") (pinfunction "GPIO.2_12") (pintype "passive"))
    )
    (net (code "47") (name "unconnected-(DD1-GPIO.3-Pad11)") (class "Default")
      (node (ref "DD1") (pin "11") (pinfunction "GPIO.3_11") (pintype "passive"))
    )
    (net (code "48") (name "unconnected-(DD1-NC-Pad10)") (class "Default")
      (node (ref "DD1") (pin "10") (pinfunction "NC_10") (pintype "passive"))
    )
    (net (code "49") (name "unconnected-(DD1-SUSPEND-Pad17)") (class "Default")
      (node (ref "DD1") (pin "17") (pinfunction "SUSPEND_17") (pintype "passive"))
    )
    (net (code "50") (name "unconnected-(DD1-~{CTS}-Pad18)") (class "Default")
      (node (ref "DD1") (pin "18") (pinfunction "~{CTS}_18") (pintype "passive"))
    )
    (net (code "51") (name "unconnected-(DD1-~{DCD}-Pad24)") (class "Default")
      (node (ref "DD1") (pin "24") (pinfunction "~{DCD}_24") (pintype "passive"))
    )
    (net (code "52") (name "unconnected-(DD1-~{DSR}-Pad22)") (class "Default")
      (node (ref "DD1") (pin "22") (pinfunction "~{DSR}_22") (pintype "passive"))
    )
    (net (code "53") (name "unconnected-(DD1-~{RI}-Pad1)") (class "Default")
      (node (ref "DD1") (pin "1") (pinfunction "~{RI}_1") (pintype "passive"))
    )
    (net (code "54") (name "unconnected-(DD1-~{SUSPEND}-Pad15)") (class "Default")
      (node (ref "DD1") (pin "15") (pinfunction "~{SUSPEND}_15") (pintype "passive"))
    )
    (net (code "55") (name "unconnected-(DD4-ADC-Pad2)") (class "Default")
      (node (ref "DD4") (pin "2") (pinfunction "ADC_2") (pintype "passive"))
    )
    (net (code "56") (name "unconnected-(DD5-ADC6-Pad19)") (class "Default")
      (node (ref "DD5") (pin "19") (pinfunction "ADC6_19") (pintype "passive"))
    )
    (net (code "57") (name "unconnected-(DD5-ADC7-Pad22)") (class "Default")
      (node (ref "DD5") (pin "22") (pinfunction "ADC7_22") (pintype "passive"))
    )
    (net (code "58") (name "unconnected-(DD5-DAP-Pad33)") (class "Default")
      (node (ref "DD5") (pin "33") (pinfunction "DAP_33") (pintype "passive"))
    )
    (net (code "59") (name "unconnected-(DD5-PB0-Pad12)") (class "Default")
      (node (ref "DD5") (pin "12") (pinfunction "PB0_12") (pintype "passive"))
    )
    (net (code "60") (name "unconnected-(DD5-PB1-Pad13)") (class "Default")
      (node (ref "DD5") (pin "13") (pinfunction "PB1_13") (pintype "passive"))
    )
    (net (code "61") (name "unconnected-(DD5-PB2_(~{SS})-Pad14)") (class "Default")
      (node (ref "DD5") (pin "14") (pinfunction "PB2_(~{SS})_14") (pintype "passive"))
    )
    (net (code "62") (name "unconnected-(DD5-PB3_(MOSI)-Pad15)") (class "Default")
      (node (ref "DD5") (pin "15") (pinfunction "PB3_(MOSI)_15") (pintype "passive"))
    )
    (net (code "63") (name "unconnected-(DD5-PB4_(MISO)-Pad16)") (class "Default")
      (node (ref "DD5") (pin "16") (pinfunction "PB4_(MISO)_16") (pintype "passive"))
    )
    (net (code "64") (name "unconnected-(DD5-PB5_(SCK)-Pad17)") (class "Default")
      (node (ref "DD5") (pin "17") (pinfunction "PB5_(SCK)_17") (pintype "passive"))
    )
    (net (code "65") (name "unconnected-(DD5-PB6_(XTAL1)-Pad7)") (class "Default")
      (node (ref "DD5") (pin "7") (pinfunction "PB6_(XTAL1)_7") (pintype "passive"))
    )
    (net (code "66") (name "unconnected-(DD5-PB7_(XTAL2)-Pad8)") (class "Default")
      (node (ref "DD5") (pin "8") (pinfunction "PB7_(XTAL2)_8") (pintype "passive"))
    )
    (net (code "67") (name "unconnected-(DD5-PD0_(RXD)-Pad30)") (class "Default")
      (node (ref "DD5") (pin "30") (pinfunction "PD0_(RXD)_30") (pintype "passive"))
    )
    (net (code "68") (name "unconnected-(DD5-PD1_(TXD)-Pad31)") (class "Default")
      (node (ref "DD5") (pin "31") (pinfunction "PD1_(TXD)_31") (pintype "passive"))
    )
    (net (code "69") (name "unconnected-(DD5-PD7-Pad11)") (class "Default")
      (node (ref "DD5") (pin "11") (pinfunction "PD7_11") (pintype "passive"))
    )
    (net (code "70") (name "unconnected-(DD6-CLKOUT-Pad7)") (class "Default")
      (node (ref "DD6") (pin "7") (pinfunction "CLKOUT_7") (pintype "passive"))
    )
    (net (code "71") (name "unconnected-(DD6-~{INT}-Pad3)") (class "Default")
      (node (ref "DD6") (pin "3") (pinfunction "~{INT}_3") (pintype "passive"))
    )
    (net (code "72") (name "unconnected-(XS1-NC-Pad4)") (class "Default")
      (node (ref "XS1") (pin "4") (pinfunction "NC_4") (pintype "passive"))
    )
    (net (code "73") (name "unconnected-(XS3-IRQ-Pad5)") (class "Default")
      (node (ref "XS3") (pin "5") (pinfunction "IRQ_5") (pintype "passive"))
    )
    (net (code "74") (name "unconnected-(XS5-NC-Pad1)") (class "Default")
      (node (ref "XS5") (pin "1") (pinfunction "NC_1") (pintype "passive"))
    )
    (net (code "75") (name "unconnected-(XS5-NC-Pad8)") (class "Default")
      (node (ref "XS5") (pin "8") (pinfunction "NC_8") (pintype "passive"))
    )
  )
)
